# 12to5VSwitcher-3A.net
KiCad netlist of a schematic drawn in Altium Designer
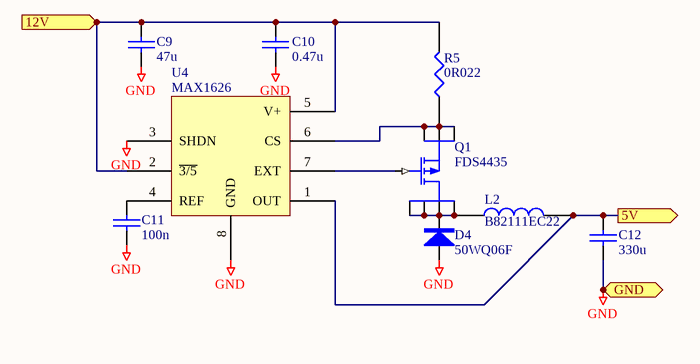
[diagram p0: 12to5VSwitcher-3A.SCHDOC]

(export (version "E")
  (design (tool "Eeschema 10.0.6"))
  (components
    (comp (ref "C9")
      (value "47u")
      (footprint "KEMET_CASED")
      (description "Capacitor")
      (libsource (lib "*") (part "CAP"))
    )
    (comp (ref "C10")
      (value "0.47u")
      (footprint "1206")
      (description "Capacitor")
      (libsource (lib "*") (part "CAP"))
    )
    (comp (ref "C11")
      (value "100n")
      (footprint "0603")
      (description "Capacitor")
      (libsource (lib "*") (part "CAP"))
    )
    (comp (ref "C12")
      (value "330u")
      (footprint "KEMET_CASED")
      (description "Capacitor")
      (libsource (lib "*") (part "CAP"))
    )
    (comp (ref "D4")
      (value "50WQ06F")
      (footprint "DPAK")
      (description "Diode")
      (libsource (lib "*") (part "50WQ06F"))
    )
    (comp (ref "L2") (value "B82111EC22") (footprint "PCH-45") (libsource (lib "*") (part "INDUCTOR")))
    (comp (ref "Q1")
      (value "FDS4435")
      (footprint "SO8")
      (description "FDS4435P Channel Mosfet")
      (libsource (lib "*") (part "SI4425DY"))
    )
    (comp (ref "R5") (value "0R022") (footprint "2512") (libsource (lib "*") (part "RES1")))
    (comp (ref "U4") (value "MAX1626") (footprint "SO8") (libsource (lib "*") (part "MAX1626")))
  )
  (nets
    (net (code "1") (name "/5V") (class "Default")
      (node (ref "C12") (pin "1") (pinfunction "1_1") (pintype "passive"))
      (node (ref "L2") (pin "2") (pinfunction "2_2") (pintype "passive"))
      (node (ref "U4") (pin "1") (pinfunction "OUT_1") (pintype "passive"))
    )
    (net (code "2") (name "/12V") (class "Default")
      (node (ref "C10") (pin "1") (pinfunction "1_1") (pintype "passive"))
      (node (ref "C9") (pin "1") (pinfunction "1_1") (pintype "passive"))
      (node (ref "R5") (pin "2") (pinfunction "2_2") (pintype "passive"))
      (node (ref "U4") (pin "2") (pinfunction "3/5_2") (pintype "passive"))
      (node (ref "U4") (pin "5") (pinfunction "V+_5") (pintype "passive"))
    )
    (net (code "3") (name "GND") (class "Default")
      (node (ref "C10") (pin "2") (pinfunction "2_2") (pintype "passive"))
      (node (ref "C11") (pin "2") (pinfunction "2_2") (pintype "passive"))
      (node (ref "C12") (pin "2") (pinfunction "2_2") (pintype "passive"))
      (node (ref "C9") (pin "2") (pinfunction "2_2") (pintype "passive"))
      (node (ref "D4") (pin "1") (pinfunction "A_1") (pintype "passive"))
      (node (ref "U4") (pin "3") (pinfunction "SHDN_3") (pintype "passive"))
      (node (ref "U4") (pin "8") (pinfunction "GND_8") (pintype "passive"))
    )
    (net (code "4") (name "Net-(D4-K)") (class "Default")
      (node (ref "D4") (pin "2") (pinfunction "K_2") (pintype "passive"))
      (node (ref "L2") (pin "1") (pinfunction "1_1") (pintype "passive"))
      (node (ref "Q1") (pin "5") (pinfunction "D_5") (pintype "bidirectional"))
      (node (ref "Q1") (pin "6") (pinfunction "D_6") (pintype "bidirectional"))
      (node (ref "Q1") (pin "7") (pinfunction "D_7") (pintype "bidirectional"))
      (node (ref "Q1") (pin "8") (pinfunction "D_8") (pintype "bidirectional"))
    )
    (net (code "5") (name "Net-(Q1-G)") (class "Default")
      (node (ref "Q1") (pin "4") (pinfunction "G_4") (pintype "input"))
      (node (ref "U4") (pin "7") (pinfunction "EXT_7") (pintype "passive"))
    )
    (net (code "6") (name "Net-(U4-CS)") (class "Default")
      (node (ref "Q1") (pin "1") (pinfunction "S_1") (pintype "bidirectional"))
      (node (ref "Q1") (pin "2") (pinfunction "S_2") (pintype "bidirectional"))
      (node (ref "Q1") (pin "3") (pinfunction "S_3") (pintype "bidirectional"))
      (node (ref "R5") (pin "1") (pinfunction "1_1") (pintype "passive"))
      (node (ref "U4") (pin "6") (pinfunction "CS_6") (pintype "passive"))
    )
    (net (code "7") (name "Net-(U4-REF)") (class "Default")
      (node (ref "C11") (pin "1") (pinfunction "1_1") (pintype "passive"))
      (node (ref "U4") (pin "4") (pinfunction "REF_4") (pintype "passive"))
    )
  )
)
